# EthIO_01_Power.net
KiCad netlist of a schematic drawn in Altium Designer
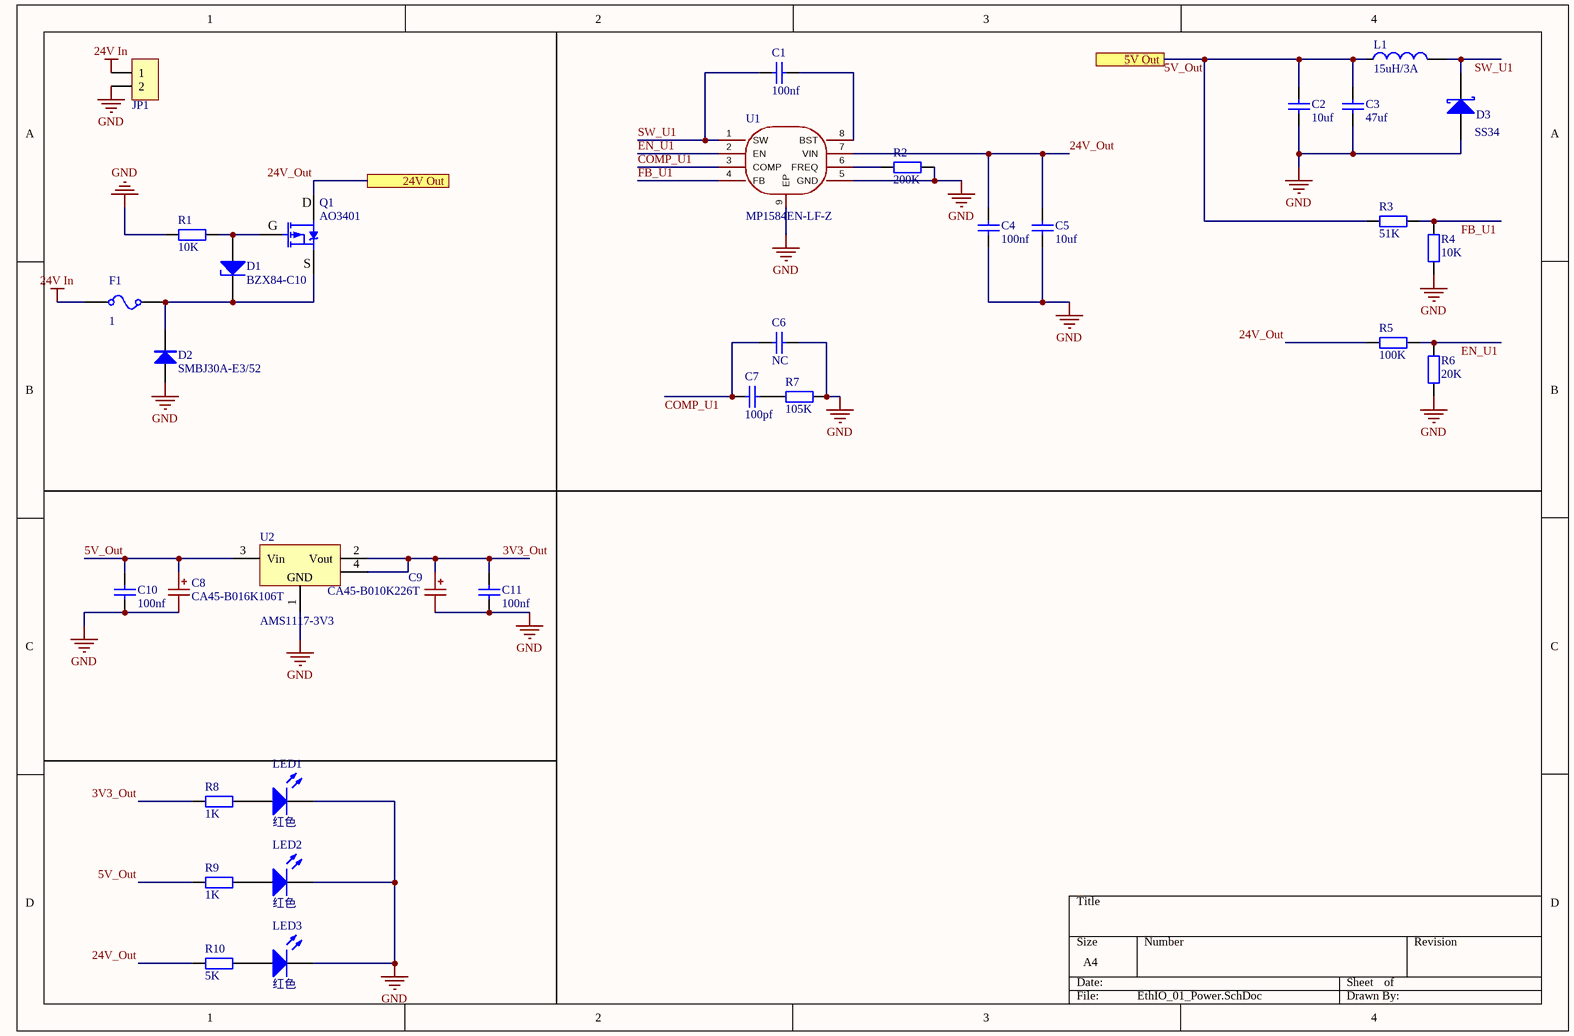
[diagram p0: EthIO_01_Power.SchDoc]

(export (version "E")
  (design (tool "Eeschema 10.0.6"))
  (components
    (comp (ref "C1")
      (value "100nf")
      (footprint "C0805_L")
      (description "贴片电容/MLCC电容")
      (libsource (lib "0.1 - 电阻-电容-电感-保险丝-晶振-晶体-磁珠-电位器-法拉电容-馈通电容") (part "C"))
    )
    (comp (ref "C2")
      (value "10uf")
      (footprint "C0805_L")
      (description "贴片电容/MLCC电容")
      (libsource (lib "0.1 - 电阻-电容-电感-保险丝-晶振-晶体-磁珠-电位器-法拉电容-馈通电容") (part "C"))
    )
    (comp (ref "C3")
      (value "47uf")
      (footprint "C0805_L")
      (description "贴片电容/MLCC电容")
      (libsource (lib "0.1 - 电阻-电容-电感-保险丝-晶振-晶体-磁珠-电位器-法拉电容-馈通电容") (part "C"))
    )
    (comp (ref "C4")
      (value "100nf")
      (footprint "C0805_L")
      (description "贴片电容/MLCC电容")
      (libsource (lib "0.1 - 电阻-电容-电感-保险丝-晶振-晶体-磁珠-电位器-法拉电容-馈通电容") (part "C"))
    )
    (comp (ref "C5")
      (value "10uf")
      (footprint "C0805_L")
      (description "贴片电容/MLCC电容")
      (libsource (lib "0.1 - 电阻-电容-电感-保险丝-晶振-晶体-磁珠-电位器-法拉电容-馈通电容") (part "C"))
    )
    (comp (ref "C6")
      (value "NC")
      (footprint "C0805_L")
      (description "贴片电容/MLCC电容")
      (libsource (lib "0.1 - 电阻-电容-电感-保险丝-晶振-晶体-磁珠-电位器-法拉电容-馈通电容") (part "C"))
    )
    (comp (ref "C7")
      (value "100pf")
      (footprint "C0805_L")
      (description "贴片电容/MLCC电容")
      (libsource (lib "0.1 - 电阻-电容-电感-保险丝-晶振-晶体-磁珠-电位器-法拉电容-馈通电容") (part "C"))
    )
    (comp (ref "C8")
      (value "CA45-B016K106T")
      (footprint "CA45-B016K106T")
      (libsource (lib "EthIO_Gateway") (part "CA45-B016K106T"))
    )
    (comp (ref "C9")
      (value "CA45-B010K226T")
      (footprint "CA45-B016K106T")
      (libsource (lib "EthIO_Gateway") (part "CA45-B016K106T"))
    )
    (comp (ref "C10")
      (value "100nf")
      (footprint "C0805_L")
      (description "贴片电容/MLCC电容")
      (libsource (lib "0.1 - 电阻-电容-电感-保险丝-晶振-晶体-磁珠-电位器-法拉电容-馈通电容") (part "C"))
    )
    (comp (ref "C11")
      (value "100nf")
      (footprint "C0805_L")
      (description "贴片电容/MLCC电容")
      (libsource (lib "0.1 - 电阻-电容-电感-保险丝-晶振-晶体-磁珠-电位器-法拉电容-馈通电容") (part "C"))
    )
    (comp (ref "D1")
      (value "BZX84-C10")
      (footprint "SOD-123")
      (description "Zener Diode")
      (libsource (lib "0.2 - 二极管-TVS-ESD-整流桥-放电管") (part "稳压二极管"))
    )
    (comp (ref "D2")
      (value "SMBJ30A-E3/52")
      (footprint "SMB")
      (description "30V 600W瞬态抑制二极管")
      (libsource (lib "0.2 - 二极管-TVS-ESD-整流桥-放电管") (part "SMBJ30A-E3/52"))
    )
    (comp (ref "D3")
      (value "SS34")
      (footprint "SMA")
      (description "肖特基二极管")
      (libsource (lib "0.2 - 二极管-TVS-ESD-整流桥-放电管") (part "D-Schottky"))
    )
    (comp (ref "F1")
      (value "Fuse")
      (fields (field (name "CURRENT") "1"))
      (libsource (lib "Simulation Generic Components") (part "Fuse"))
    )
    (comp (ref "JP1")
      (value "HDR-1X2")
      (footprint "KF128-3.81-2P")
      (description "2P接插件")
      (libsource (lib "5.7 - 3.81mm连接器(KF128-KF2EDGVHM)") (part "Header 2"))
    )
    (comp (ref "L1")
      (value "15uH/3A")
      (footprint "L0805")
      (description "贴片小功率电感")
      (libsource (lib "0.1 - 电阻-电容-电感-保险丝-晶振-晶体-磁珠-电位器-法拉电容-馈通电容") (part "L"))
    )
    (comp (ref "LED1")
      (value "红色")
      (footprint "LED0805_G")
      (description "贴片LED")
      (libsource (lib "0.3 - LED发光二极管-IR二极管_接收管-光耦") (part "LED"))
    )
    (comp (ref "LED2")
      (value "红色")
      (footprint "LED0805_G")
      (description "贴片LED")
      (libsource (lib "0.3 - LED发光二极管-IR二极管_接收管-光耦") (part "LED"))
    )
    (comp (ref "LED3")
      (value "红色")
      (footprint "LED0805_G")
      (description "贴片LED")
      (libsource (lib "0.3 - LED发光二极管-IR二极管_接收管-光耦") (part "LED"))
    )
    (comp (ref "Q1")
      (value "AO3401")
      (footprint "SOT23-3N")
      (description "P沟道 30V/4.2A")
      (libsource (lib "0.4 - 三极管-场效应管-可控硅") (part "AO3401"))
    )
    (comp (ref "R1")
      (value "10K")
      (footprint "R0805_L")
      (description "贴片电阻")
      (libsource (lib "0.1 - 电阻-电容-电感-保险丝-晶振-晶体-磁珠-电位器-法拉电容-馈通电容") (part "R"))
    )
    (comp (ref "R2")
      (value "200K")
      (footprint "R0805_L")
      (description "贴片电阻")
      (libsource (lib "0.1 - 电阻-电容-电感-保险丝-晶振-晶体-磁珠-电位器-法拉电容-馈通电容") (part "R"))
    )
    (comp (ref "R3")
      (value "51K")
      (footprint "R0805_L")
      (description "贴片电阻")
      (libsource (lib "0.1 - 电阻-电容-电感-保险丝-晶振-晶体-磁珠-电位器-法拉电容-馈通电容") (part "R"))
    )
    (comp (ref "R4")
      (value "10K")
      (footprint "R0805_L")
      (description "贴片电阻")
      (libsource (lib "0.1 - 电阻-电容-电感-保险丝-晶振-晶体-磁珠-电位器-法拉电容-馈通电容") (part "R"))
    )
    (comp (ref "R5")
      (value "100K")
      (footprint "R0805_L")
      (description "贴片电阻")
      (libsource (lib "0.1 - 电阻-电容-电感-保险丝-晶振-晶体-磁珠-电位器-法拉电容-馈通电容") (part "R"))
    )
    (comp (ref "R6")
      (value "20K")
      (footprint "R0805_L")
      (description "贴片电阻")
      (libsource (lib "0.1 - 电阻-电容-电感-保险丝-晶振-晶体-磁珠-电位器-法拉电容-馈通电容") (part "R"))
    )
    (comp (ref "R7")
      (value "105K")
      (footprint "R0805_L")
      (description "贴片电阻")
      (libsource (lib "0.1 - 电阻-电容-电感-保险丝-晶振-晶体-磁珠-电位器-法拉电容-馈通电容") (part "R"))
    )
    (comp (ref "R8")
      (value "1K")
      (footprint "R0805_L")
      (description "贴片电阻")
      (libsource (lib "0.1 - 电阻-电容-电感-保险丝-晶振-晶体-磁珠-电位器-法拉电容-馈通电容") (part "R"))
    )
    (comp (ref "R9")
      (value "1K")
      (footprint "R0805_L")
      (description "贴片电阻")
      (libsource (lib "0.1 - 电阻-电容-电感-保险丝-晶振-晶体-磁珠-电位器-法拉电容-馈通电容") (part "R"))
    )
    (comp (ref "R10")
      (value "5K")
      (footprint "R0805_L")
      (description "贴片电阻")
      (libsource (lib "0.1 - 电阻-电容-电感-保险丝-晶振-晶体-磁珠-电位器-法拉电容-馈通电容") (part "R"))
    )
    (comp (ref "U1")
      (value "MP1584EN-LF-Z")
      (footprint "MP1584EN-LF-Z")
      (libsource (lib "EthIO_Gateway") (part "MP1584EN-LF-Z"))
    )
    (comp (ref "U2")
      (value "AMS1117-3V3")
      (footprint "SOT223_L")
      (description "三端稳压芯片")
      (libsource (lib "0.7 - 电源类芯片") (part "AMS1117"))
    )
  )
  (nets
    (net (code "1") (name "/3V3_Out") (class "Default")
      (node (ref "C11") (pin "2") (pinfunction "2_2") (pintype "passive"))
      (node (ref "C9") (pin "1") (pinfunction "1_1") (pintype "passive"))
      (node (ref "R8") (pin "1") (pinfunction "1_1") (pintype "passive"))
      (node (ref "U2") (pin "2") (pinfunction "Vout_2") (pintype "passive"))
      (node (ref "U2") (pin "4") (pinfunction "GND_4") (pintype "passive"))
    )
    (net (code "2") (name "/5V_Out") (class "Default")
      (node (ref "C10") (pin "2") (pinfunction "2_2") (pintype "passive"))
      (node (ref "C2") (pin "2") (pinfunction "2_2") (pintype "passive"))
      (node (ref "C3") (pin "2") (pinfunction "2_2") (pintype "passive"))
      (node (ref "C8") (pin "1") (pinfunction "1_1") (pintype "passive"))
      (node (ref "L1") (pin "1") (pinfunction "1_1") (pintype "passive"))
      (node (ref "R3") (pin "1") (pinfunction "1_1") (pintype "passive"))
      (node (ref "R9") (pin "1") (pinfunction "1_1") (pintype "passive"))
      (node (ref "U2") (pin "3") (pinfunction "Vin_3") (pintype "passive"))
    )
    (net (code "3") (name "/24V_Out") (class "Default")
      (node (ref "C4") (pin "2") (pinfunction "2_2") (pintype "passive"))
      (node (ref "C5") (pin "2") (pinfunction "2_2") (pintype "passive"))
      (node (ref "Q1") (pin "3") (pinfunction "D_3") (pintype "passive"))
      (node (ref "R10") (pin "1") (pinfunction "1_1") (pintype "passive"))
      (node (ref "R5") (pin "1") (pinfunction "1_1") (pintype "passive"))
      (node (ref "U1") (pin "7") (pinfunction "VIN_7") (pintype "passive"))
    )
    (net (code "4") (name "/COMP_U1") (class "Default")
      (node (ref "C6") (pin "2") (pinfunction "2_2") (pintype "passive"))
      (node (ref "C7") (pin "2") (pinfunction "2_2") (pintype "passive"))
      (node (ref "U1") (pin "3") (pinfunction "COMP_3") (pintype "passive"))
    )
    (net (code "5") (name "/EN_U1") (class "Default")
      (node (ref "R5") (pin "2") (pinfunction "2_2") (pintype "passive"))
      (node (ref "R6") (pin "1") (pinfunction "1_1") (pintype "passive"))
      (node (ref "U1") (pin "2") (pinfunction "EN_2") (pintype "passive"))
    )
    (net (code "6") (name "/FB_U1") (class "Default")
      (node (ref "R3") (pin "2") (pinfunction "2_2") (pintype "passive"))
      (node (ref "R4") (pin "2") (pinfunction "2_2") (pintype "passive"))
      (node (ref "U1") (pin "4") (pinfunction "FB_4") (pintype "passive"))
    )
    (net (code "7") (name "/SW_U1") (class "Default")
      (node (ref "C1") (pin "2") (pinfunction "2_2") (pintype "passive"))
      (node (ref "D3") (pin "2") (pinfunction "K_2") (pintype "passive"))
      (node (ref "L1") (pin "2") (pinfunction "2_2") (pintype "passive"))
      (node (ref "U1") (pin "1") (pinfunction "SW_1") (pintype "passive"))
    )
    (net (code "8") (name "24V In") (class "Default")
      (node (ref "F1") (pin "2") (pinfunction "2_2") (pintype "passive"))
      (node (ref "JP1") (pin "1") (pinfunction "1_1") (pintype "passive"))
    )
    (net (code "9") (name "GND") (class "Default")
      (node (ref "C10") (pin "1") (pinfunction "1_1") (pintype "passive"))
      (node (ref "C11") (pin "1") (pinfunction "1_1") (pintype "passive"))
      (node (ref "C2") (pin "1") (pinfunction "1_1") (pintype "passive"))
      (node (ref "C3") (pin "1") (pinfunction "1_1") (pintype "passive"))
      (node (ref "C4") (pin "1") (pinfunction "1_1") (pintype "passive"))
      (node (ref "C5") (pin "1") (pinfunction "1_1") (pintype "passive"))
      (node (ref "C6") (pin "1") (pinfunction "1_1") (pintype "passive"))
      (node (ref "C8") (pin "2") (pinfunction "2_2") (pintype "passive"))
      (node (ref "C9") (pin "2") (pinfunction "2_2") (pintype "passive"))
      (node (ref "D2") (pin "1") (pinfunction "A_1") (pintype "passive"))
      (node (ref "D3") (pin "1") (pinfunction "A_1") (pintype "passive"))
      (node (ref "JP1") (pin "2") (pinfunction "2_2") (pintype "passive"))
      (node (ref "LED1") (pin "2") (pinfunction "K_2") (pintype "passive"))
      (node (ref "LED2") (pin "2") (pinfunction "K_2") (pintype "passive"))
      (node (ref "LED3") (pin "2") (pinfunction "K_2") (pintype "passive"))
      (node (ref "R1") (pin "1") (pinfunction "1_1") (pintype "passive"))
      (node (ref "R2") (pin "2") (pinfunction "2_2") (pintype "passive"))
      (node (ref "R4") (pin "1") (pinfunction "1_1") (pintype "passive"))
      (node (ref "R6") (pin "2") (pinfunction "2_2") (pintype "passive"))
      (node (ref "R7") (pin "1") (pinfunction "1_1") (pintype "passive"))
      (node (ref "U1") (pin "5") (pinfunction "GND_5") (pintype "passive"))
      (node (ref "U1") (pin "9") (pinfunction "EP_9") (pintype "passive"))
      (node (ref "U2") (pin "1") (pinfunction "GND_1") (pintype "passive"))
    )
    (net (code "10") (name "Net-(C7-Pad1)") (class "Default")
      (node (ref "C7") (pin "1") (pinfunction "1_1") (pintype "passive"))
      (node (ref "R7") (pin "2") (pinfunction "2_2") (pintype "passive"))
    )
    (net (code "11") (name "Net-(D1-A)") (class "Default")
      (node (ref "D1") (pin "1") (pinfunction "A_1") (pintype "passive"))
      (node (ref "Q1") (pin "1") (pinfunction "G_1") (pintype "passive"))
      (node (ref "R1") (pin "2") (pinfunction "2_2") (pintype "passive"))
    )
    (net (code "12") (name "Net-(D1-K)") (class "Default")
      (node (ref "D1") (pin "2") (pinfunction "K_2") (pintype "passive"))
      (node (ref "D2") (pin "2") (pinfunction "K_2") (pintype "passive"))
      (node (ref "F1") (pin "1") (pinfunction "1_1") (pintype "passive"))
      (node (ref "Q1") (pin "2") (pinfunction "S_2") (pintype "passive"))
    )
    (net (code "13") (name "Net-(LED1-A)") (class "Default")
      (node (ref "LED1") (pin "1") (pinfunction "A_1") (pintype "passive"))
      (node (ref "R8") (pin "2") (pinfunction "2_2") (pintype "passive"))
    )
    (net (code "14") (name "Net-(LED2-A)") (class "Default")
      (node (ref "LED2") (pin "1") (pinfunction "A_1") (pintype "passive"))
      (node (ref "R9") (pin "2") (pinfunction "2_2") (pintype "passive"))
    )
    (net (code "15") (name "Net-(LED3-A)") (class "Default")
      (node (ref "LED3") (pin "1") (pinfunction "A_1") (pintype "passive"))
      (node (ref "R10") (pin "2") (pinfunction "2_2") (pintype "passive"))
    )
    (net (code "16") (name "Net-(U1-BST)") (class "Default")
      (node (ref "C1") (pin "1") (pinfunction "1_1") (pintype "passive"))
      (node (ref "U1") (pin "8") (pinfunction "BST_8") (pintype "passive"))
    )
    (net (code "17") (name "Net-(U1-FREQ)") (class "Default")
      (node (ref "R2") (pin "1") (pinfunction "1_1") (pintype "passive"))
      (node (ref "U1") (pin "6") (pinfunction "FREQ_6") (pintype "passive"))
    )
  )
)
